# D12_1_0.net
KiCad netlist of a schematic drawn in EAGLE
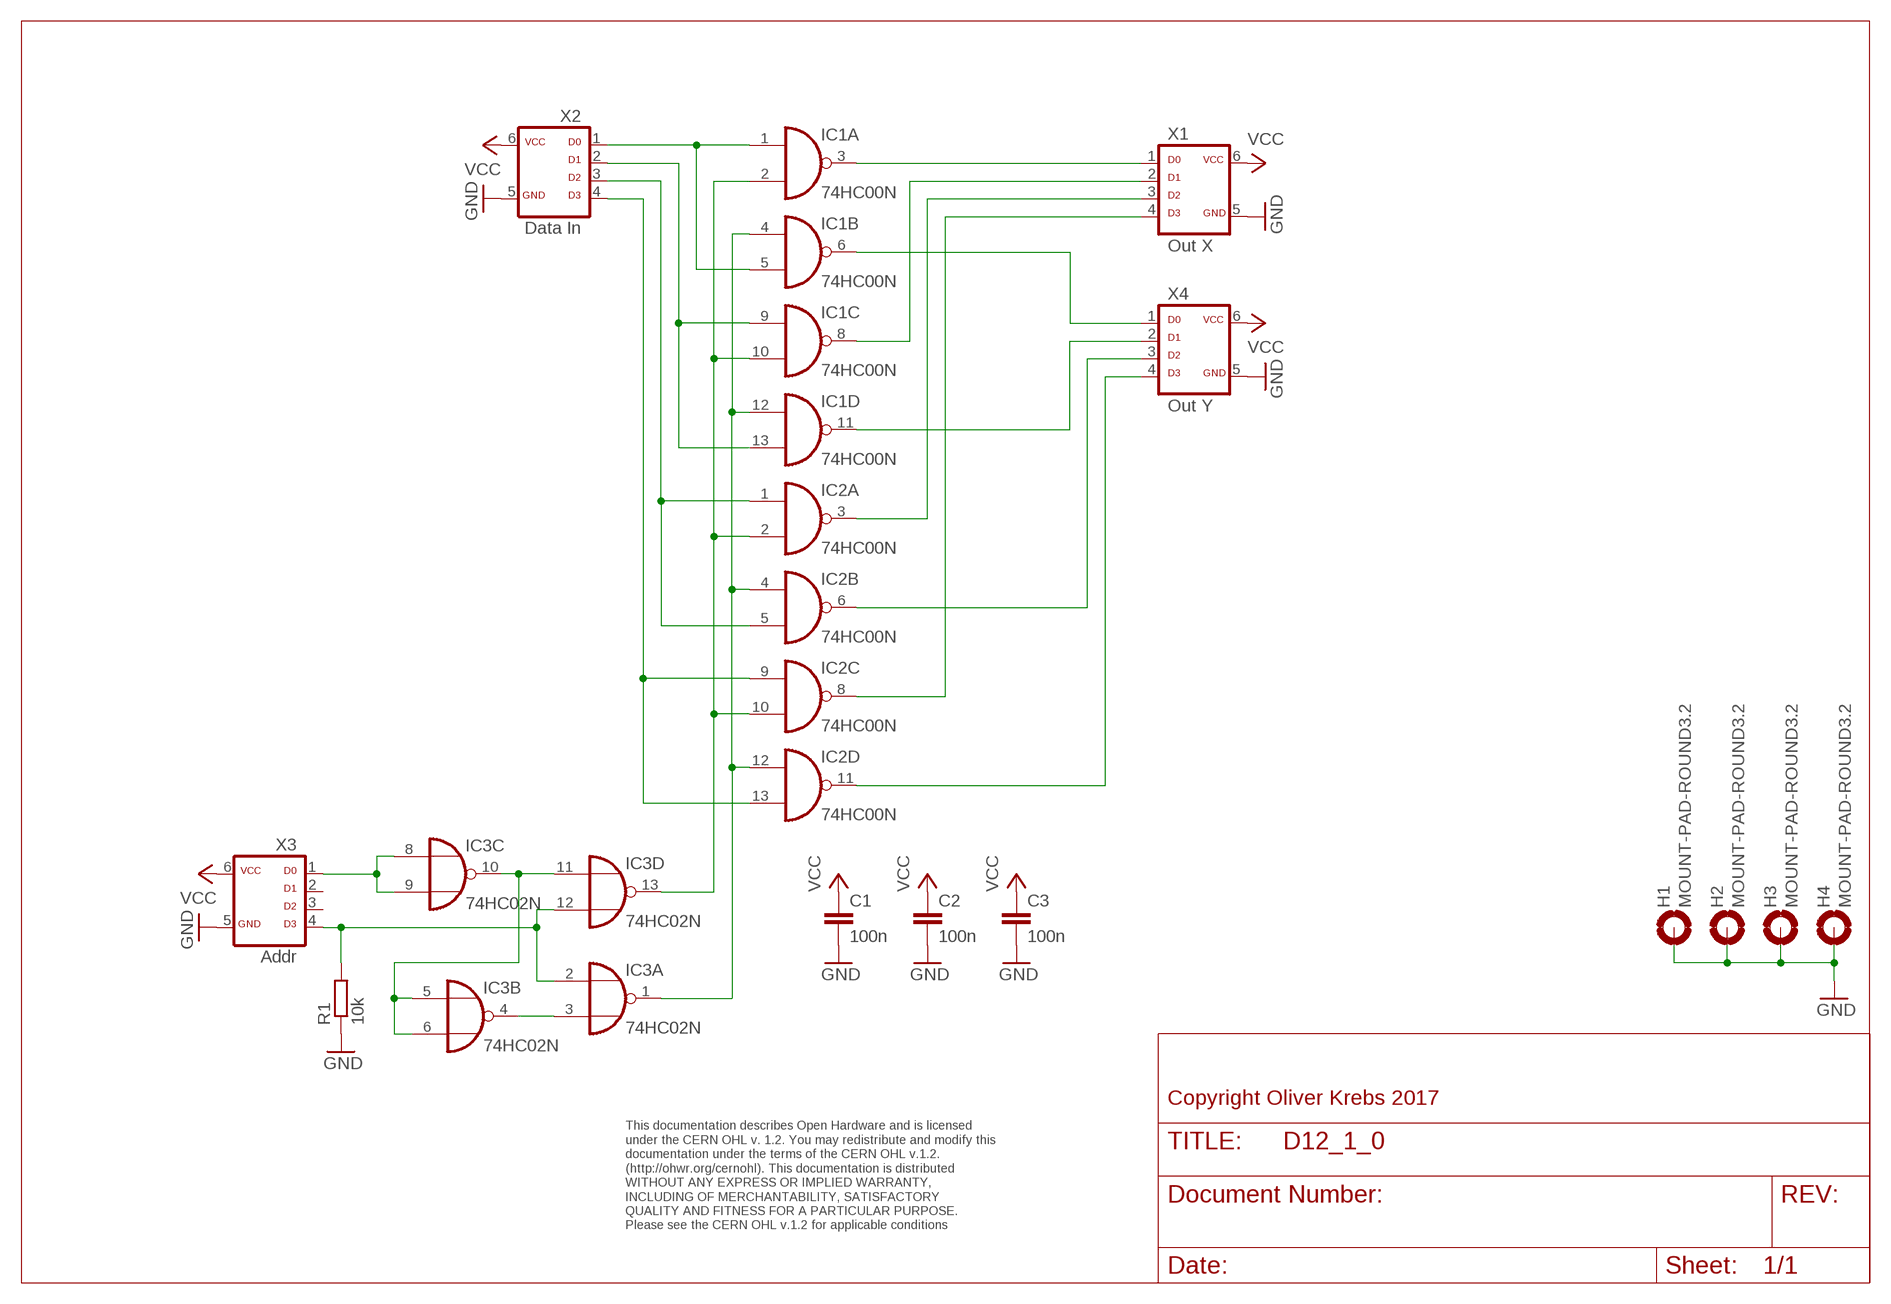
[diagram p0: schematic, sheet 1]

(export (version "E")
  (design (tool "Eeschema 10.0.6"))
  (components
    (comp (ref "C1")
      (value "100n")
      (footprint "eagle-import:C050-025X075")
      (libsource (lib "eagle-import") (part "C-EU050-025X075"))
    )
    (comp (ref "C2")
      (value "100n")
      (footprint "eagle-import:C050-025X075")
      (libsource (lib "eagle-import") (part "C-EU050-025X075"))
    )
    (comp (ref "C3")
      (value "100n")
      (footprint "eagle-import:C050-025X075")
      (libsource (lib "eagle-import") (part "C-EU050-025X075"))
    )
    (comp (ref "H1")
      (value "MOUNT-PAD-ROUND3.2")
      (footprint "eagle-import:3,2-PAD")
      (libsource (lib "eagle-import") (part "MOUNT-PAD-ROUND3.2"))
    )
    (comp (ref "H2")
      (value "MOUNT-PAD-ROUND3.2")
      (footprint "eagle-import:3,2-PAD")
      (libsource (lib "eagle-import") (part "MOUNT-PAD-ROUND3.2"))
    )
    (comp (ref "H3")
      (value "MOUNT-PAD-ROUND3.2")
      (footprint "eagle-import:3,2-PAD")
      (libsource (lib "eagle-import") (part "MOUNT-PAD-ROUND3.2"))
    )
    (comp (ref "H4")
      (value "MOUNT-PAD-ROUND3.2")
      (footprint "eagle-import:3,2-PAD")
      (libsource (lib "eagle-import") (part "MOUNT-PAD-ROUND3.2"))
    )
    (comp (ref "IC1")
      (value "74HC00N")
      (footprint "eagle-import:DIL14")
      (libsource (lib "eagle-import") (part "7400NHC"))
    )
    (comp (ref "IC2")
      (value "74HC00N")
      (footprint "eagle-import:DIL14")
      (libsource (lib "eagle-import") (part "7400NHC"))
    )
    (comp (ref "IC3")
      (value "74HC02N")
      (footprint "eagle-import:DIL14")
      (libsource (lib "eagle-import") (part "7402NHC"))
    )
    (comp (ref "R1")
      (value "10k")
      (footprint "eagle-import:0207_10")
      (libsource (lib "eagle-import") (part "R-EU_0207/10"))
    )
    (comp (ref "X1")
      (value "Out X")
      (footprint "eagle-import:ML-6")
      (libsource (lib "eagle-import") (part "ML6D"))
    )
    (comp (ref "X2")
      (value "Data In")
      (footprint "eagle-import:ML-6")
      (libsource (lib "eagle-import") (part "ML6D"))
    )
    (comp (ref "X3")
      (value "Addr")
      (footprint "eagle-import:ML-6")
      (libsource (lib "eagle-import") (part "ML6D"))
    )
    (comp (ref "X4")
      (value "Out Y")
      (footprint "eagle-import:ML-6")
      (libsource (lib "eagle-import") (part "ML6D"))
    )
  )
  (nets
    (net (code "1") (name "GND") (class "Default")
      (node (ref "C1") (pin "2") (pinfunction "2_2") (pintype "passive"))
      (node (ref "C2") (pin "2") (pinfunction "2_2") (pintype "passive"))
      (node (ref "C3") (pin "2") (pinfunction "2_2") (pintype "passive"))
      (node (ref "H1") (pin "B3,2") (pinfunction "MOUNT_B3,2") (pintype "passive"))
      (node (ref "H2") (pin "B3,2") (pinfunction "MOUNT_B3,2") (pintype "passive"))
      (node (ref "H3") (pin "B3,2") (pinfunction "MOUNT_B3,2") (pintype "passive"))
      (node (ref "H4") (pin "B3,2") (pinfunction "MOUNT_B3,2") (pintype "passive"))
      (node (ref "R1") (pin "1") (pinfunction "1_1") (pintype "passive"))
      (node (ref "X1") (pin "5") (pinfunction "5_5") (pintype "passive"))
      (node (ref "X2") (pin "5") (pinfunction "5_5") (pintype "passive"))
      (node (ref "X3") (pin "5") (pinfunction "5_5") (pintype "passive"))
      (node (ref "X4") (pin "5") (pinfunction "5_5") (pintype "passive"))
    )
    (net (code "2") (name "Net-(IC1A-I0)") (class "Default")
      (node (ref "IC1") (pin "1") (pinfunction "I0_1") (pintype "input"))
      (node (ref "IC1") (pin "5") (pinfunction "I1_5") (pintype "input"))
      (node (ref "X2") (pin "1") (pinfunction "1_1") (pintype "passive"))
    )
    (net (code "3") (name "Net-(IC1A-I1)") (class "Default")
      (node (ref "IC1") (pin "10") (pinfunction "I1_10") (pintype "input"))
      (node (ref "IC1") (pin "2") (pinfunction "I1_2") (pintype "input"))
      (node (ref "IC2") (pin "10") (pinfunction "I1_10") (pintype "input"))
      (node (ref "IC2") (pin "2") (pinfunction "I1_2") (pintype "input"))
      (node (ref "IC3") (pin "13") (pinfunction "O_13") (pintype "output"))
    )
    (net (code "4") (name "Net-(IC1A-O)") (class "Default")
      (node (ref "IC1") (pin "3") (pinfunction "O_3") (pintype "output"))
      (node (ref "X1") (pin "1") (pinfunction "1_1") (pintype "passive"))
    )
    (net (code "5") (name "Net-(IC1B-I0)") (class "Default")
      (node (ref "IC1") (pin "12") (pinfunction "I0_12") (pintype "input"))
      (node (ref "IC1") (pin "4") (pinfunction "I0_4") (pintype "input"))
      (node (ref "IC2") (pin "12") (pinfunction "I0_12") (pintype "input"))
      (node (ref "IC2") (pin "4") (pinfunction "I0_4") (pintype "input"))
      (node (ref "IC3") (pin "1") (pinfunction "O_1") (pintype "output"))
    )
    (net (code "6") (name "Net-(IC1B-O)") (class "Default")
      (node (ref "IC1") (pin "6") (pinfunction "O_6") (pintype "output"))
      (node (ref "X4") (pin "1") (pinfunction "1_1") (pintype "passive"))
    )
    (net (code "7") (name "Net-(IC1C-I0)") (class "Default")
      (node (ref "IC1") (pin "13") (pinfunction "I1_13") (pintype "input"))
      (node (ref "IC1") (pin "9") (pinfunction "I0_9") (pintype "input"))
      (node (ref "X2") (pin "2") (pinfunction "2_2") (pintype "passive"))
    )
    (net (code "8") (name "Net-(IC1C-O)") (class "Default")
      (node (ref "IC1") (pin "8") (pinfunction "O_8") (pintype "output"))
      (node (ref "X1") (pin "2") (pinfunction "2_2") (pintype "passive"))
    )
    (net (code "9") (name "Net-(IC1D-O)") (class "Default")
      (node (ref "IC1") (pin "11") (pinfunction "O_11") (pintype "output"))
      (node (ref "X4") (pin "2") (pinfunction "2_2") (pintype "passive"))
    )
    (net (code "10") (name "Net-(IC2A-I0)") (class "Default")
      (node (ref "IC2") (pin "1") (pinfunction "I0_1") (pintype "input"))
      (node (ref "IC2") (pin "5") (pinfunction "I1_5") (pintype "input"))
      (node (ref "X2") (pin "3") (pinfunction "3_3") (pintype "passive"))
    )
    (net (code "11") (name "Net-(IC2A-O)") (class "Default")
      (node (ref "IC2") (pin "3") (pinfunction "O_3") (pintype "output"))
      (node (ref "X1") (pin "3") (pinfunction "3_3") (pintype "passive"))
    )
    (net (code "12") (name "Net-(IC2B-O)") (class "Default")
      (node (ref "IC2") (pin "6") (pinfunction "O_6") (pintype "output"))
      (node (ref "X4") (pin "3") (pinfunction "3_3") (pintype "passive"))
    )
    (net (code "13") (name "Net-(IC2C-I0)") (class "Default")
      (node (ref "IC2") (pin "13") (pinfunction "I1_13") (pintype "input"))
      (node (ref "IC2") (pin "9") (pinfunction "I0_9") (pintype "input"))
      (node (ref "X2") (pin "4") (pinfunction "4_4") (pintype "passive"))
    )
    (net (code "14") (name "Net-(IC2C-O)") (class "Default")
      (node (ref "IC2") (pin "8") (pinfunction "O_8") (pintype "output"))
      (node (ref "X1") (pin "4") (pinfunction "4_4") (pintype "passive"))
    )
    (net (code "15") (name "Net-(IC2D-O)") (class "Default")
      (node (ref "IC2") (pin "11") (pinfunction "O_11") (pintype "output"))
      (node (ref "X4") (pin "4") (pinfunction "4_4") (pintype "passive"))
    )
    (net (code "16") (name "Net-(IC3A-I0)") (class "Default")
      (node (ref "IC3") (pin "12") (pinfunction "I1_12") (pintype "input"))
      (node (ref "IC3") (pin "2") (pinfunction "I0_2") (pintype "input"))
      (node (ref "R1") (pin "2") (pinfunction "2_2") (pintype "passive"))
      (node (ref "X3") (pin "4") (pinfunction "4_4") (pintype "passive"))
    )
    (net (code "17") (name "Net-(IC3A-I1)") (class "Default")
      (node (ref "IC3") (pin "3") (pinfunction "I1_3") (pintype "input"))
      (node (ref "IC3") (pin "4") (pinfunction "O_4") (pintype "output"))
    )
    (net (code "18") (name "Net-(IC3B-I0)") (class "Default")
      (node (ref "IC3") (pin "10") (pinfunction "O_10") (pintype "output"))
      (node (ref "IC3") (pin "11") (pinfunction "I0_11") (pintype "input"))
      (node (ref "IC3") (pin "5") (pinfunction "I0_5") (pintype "input"))
      (node (ref "IC3") (pin "6") (pinfunction "I1_6") (pintype "input"))
    )
    (net (code "19") (name "Net-(IC3C-I0)") (class "Default")
      (node (ref "IC3") (pin "8") (pinfunction "I0_8") (pintype "input"))
      (node (ref "IC3") (pin "9") (pinfunction "I1_9") (pintype "input"))
      (node (ref "X3") (pin "1") (pinfunction "1_1") (pintype "passive"))
    )
    (net (code "20") (name "VCC") (class "Default")
      (node (ref "C1") (pin "1") (pinfunction "1_1") (pintype "passive"))
      (node (ref "C2") (pin "1") (pinfunction "1_1") (pintype "passive"))
      (node (ref "C3") (pin "1") (pinfunction "1_1") (pintype "passive"))
      (node (ref "X1") (pin "6") (pinfunction "6_6") (pintype "passive"))
      (node (ref "X2") (pin "6") (pinfunction "6_6") (pintype "passive"))
      (node (ref "X3") (pin "6") (pinfunction "6_6") (pintype "passive"))
      (node (ref "X4") (pin "6") (pinfunction "6_6") (pintype "passive"))
    )
    (net (code "21") (name "unconnected-(X3-Pad2)") (class "Default")
      (node (ref "X3") (pin "2") (pinfunction "2_2") (pintype "passive"))
    )
    (net (code "22") (name "unconnected-(X3-Pad3)") (class "Default")
      (node (ref "X3") (pin "3") (pinfunction "3_3") (pintype "passive"))
    )
  )
)
